# ControllerBoard.net
KiCad netlist of a schematic drawn in EAGLE
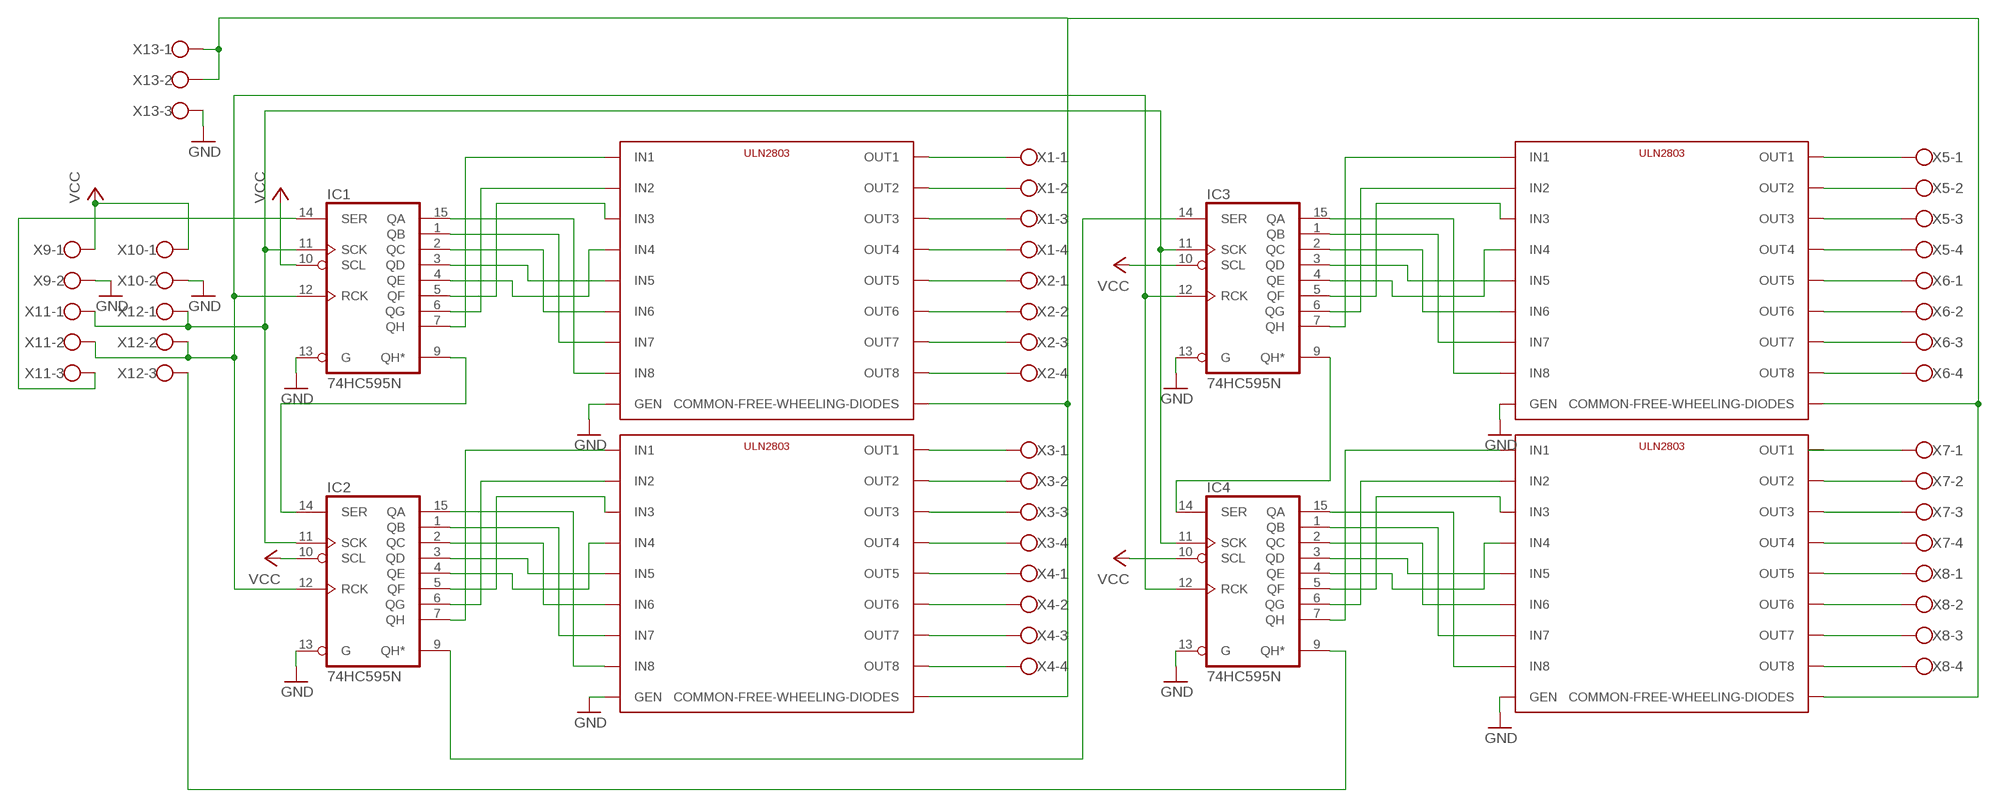
[diagram p0: schematic, sheet 1]

(export (version "E")
  (design (tool "Eeschema 10.0.6"))
  (components
    (comp (ref "IC1")
      (value "74HC595N")
      (footprint "eagle-import:DIL16")
      (libsource (lib "eagle-import") (part "74595NHC"))
    )
    (comp (ref "IC2")
      (value "74HC595N")
      (footprint "eagle-import:DIL16")
      (libsource (lib "eagle-import") (part "74595NHC"))
    )
    (comp (ref "IC3")
      (value "74HC595N")
      (footprint "eagle-import:DIL16")
      (libsource (lib "eagle-import") (part "74595NHC"))
    )
    (comp (ref "IC4")
      (value "74HC595N")
      (footprint "eagle-import:DIL16")
      (libsource (lib "eagle-import") (part "74595NHC"))
    )
    (comp (ref "U$1")
      (value "ULN2803")
      (footprint "eagle-import:P-DIP")
      (libsource (lib "eagle-import") (part "ULN2803"))
    )
    (comp (ref "U$2")
      (value "ULN2803")
      (footprint "eagle-import:P-DIP")
      (libsource (lib "eagle-import") (part "ULN2803"))
    )
    (comp (ref "U$3")
      (value "ULN2803")
      (footprint "eagle-import:P-DIP")
      (libsource (lib "eagle-import") (part "ULN2803"))
    )
    (comp (ref "U$4")
      (value "ULN2803")
      (footprint "eagle-import:P-DIP")
      (libsource (lib "eagle-import") (part "ULN2803"))
    )
    (comp (ref "X1")
      (value "W237-4")
      (footprint "eagle-import:W237-4")
      (libsource (lib "eagle-import") (part "W237-4"))
    )
    (comp (ref "X2")
      (value "W237-4")
      (footprint "eagle-import:W237-4")
      (libsource (lib "eagle-import") (part "W237-4"))
    )
    (comp (ref "X3")
      (value "W237-4")
      (footprint "eagle-import:W237-4")
      (libsource (lib "eagle-import") (part "W237-4"))
    )
    (comp (ref "X4")
      (value "W237-4")
      (footprint "eagle-import:W237-4")
      (libsource (lib "eagle-import") (part "W237-4"))
    )
    (comp (ref "X5")
      (value "W237-4")
      (footprint "eagle-import:W237-4")
      (libsource (lib "eagle-import") (part "W237-4"))
    )
    (comp (ref "X6")
      (value "W237-4")
      (footprint "eagle-import:W237-4")
      (libsource (lib "eagle-import") (part "W237-4"))
    )
    (comp (ref "X7")
      (value "W237-4")
      (footprint "eagle-import:W237-4")
      (libsource (lib "eagle-import") (part "W237-4"))
    )
    (comp (ref "X8")
      (value "W237-4")
      (footprint "eagle-import:W237-4")
      (libsource (lib "eagle-import") (part "W237-4"))
    )
    (comp (ref "X9")
      (value "W237-102")
      (footprint "eagle-import:W237-102")
      (fields (field (name "MPN") "237-102"))
      (libsource (lib "eagle-import") (part "W237-102"))
    )
    (comp (ref "X10")
      (value "W237-102")
      (footprint "eagle-import:W237-102")
      (fields (field (name "MPN") "237-102"))
      (libsource (lib "eagle-import") (part "W237-102"))
    )
    (comp (ref "X11")
      (value "W237-103")
      (footprint "eagle-import:W237-103")
      (fields (field (name "MPN") "237-103"))
      (libsource (lib "eagle-import") (part "W237-103"))
    )
    (comp (ref "X12")
      (value "W237-103")
      (footprint "eagle-import:W237-103")
      (fields (field (name "MPN") "237-103"))
      (libsource (lib "eagle-import") (part "W237-103"))
    )
    (comp (ref "X13")
      (value "W237-103")
      (footprint "eagle-import:W237-103")
      (fields (field (name "MPN") "237-103"))
      (libsource (lib "eagle-import") (part "W237-103"))
    )
  )
  (nets
    (net (code "1") (name "GND") (class "Default")
      (node (ref "IC1") (pin "13") (pinfunction "G_13") (pintype "input"))
      (node (ref "IC2") (pin "13") (pinfunction "G_13") (pintype "input"))
      (node (ref "IC3") (pin "13") (pinfunction "G_13") (pintype "input"))
      (node (ref "IC4") (pin "13") (pinfunction "G_13") (pintype "input"))
      (node (ref "U$1") (pin "GEN") (pinfunction "GEN_GEN") (pintype "power_in"))
      (node (ref "U$2") (pin "GEN") (pinfunction "GEN_GEN") (pintype "power_in"))
      (node (ref "U$3") (pin "GEN") (pinfunction "GEN_GEN") (pintype "power_in"))
      (node (ref "U$4") (pin "GEN") (pinfunction "GEN_GEN") (pintype "power_in"))
      (node (ref "X10") (pin "2") (pinfunction "KL_2") (pintype "passive"))
      (node (ref "X13") (pin "3") (pinfunction "KL_3") (pintype "passive"))
      (node (ref "X9") (pin "2") (pinfunction "KL_2") (pintype "passive"))
    )
    (net (code "2") (name "Net-(IC1A-QA)") (class "Default")
      (node (ref "IC1") (pin "15") (pinfunction "QA_15") (pintype "tri_state"))
      (node (ref "U$1") (pin "IN8") (pinfunction "IN8_IN8") (pintype "input"))
    )
    (net (code "3") (name "Net-(IC1A-QB)") (class "Default")
      (node (ref "IC1") (pin "1") (pinfunction "QB_1") (pintype "tri_state"))
      (node (ref "U$1") (pin "IN7") (pinfunction "IN7_IN7") (pintype "input"))
    )
    (net (code "4") (name "Net-(IC1A-QC)") (class "Default")
      (node (ref "IC1") (pin "2") (pinfunction "QC_2") (pintype "tri_state"))
      (node (ref "U$1") (pin "IN6") (pinfunction "IN6_IN6") (pintype "input"))
    )
    (net (code "5") (name "Net-(IC1A-QD)") (class "Default")
      (node (ref "IC1") (pin "3") (pinfunction "QD_3") (pintype "tri_state"))
      (node (ref "U$1") (pin "IN5") (pinfunction "IN5_IN5") (pintype "input"))
    )
    (net (code "6") (name "Net-(IC1A-QE)") (class "Default")
      (node (ref "IC1") (pin "4") (pinfunction "QE_4") (pintype "tri_state"))
      (node (ref "U$1") (pin "IN4") (pinfunction "IN4_IN4") (pintype "input"))
    )
    (net (code "7") (name "Net-(IC1A-QF)") (class "Default")
      (node (ref "IC1") (pin "5") (pinfunction "QF_5") (pintype "tri_state"))
      (node (ref "U$1") (pin "IN3") (pinfunction "IN3_IN3") (pintype "input"))
    )
    (net (code "8") (name "Net-(IC1A-QG)") (class "Default")
      (node (ref "IC1") (pin "6") (pinfunction "QG_6") (pintype "tri_state"))
      (node (ref "U$1") (pin "IN2") (pinfunction "IN2_IN2") (pintype "input"))
    )
    (net (code "9") (name "Net-(IC1A-QH)") (class "Default")
      (node (ref "IC1") (pin "7") (pinfunction "QH_7") (pintype "tri_state"))
      (node (ref "U$1") (pin "IN1") (pinfunction "IN1_IN1") (pintype "input"))
    )
    (net (code "10") (name "Net-(IC1A-QH*)") (class "Default")
      (node (ref "IC1") (pin "9") (pinfunction "QH*_9") (pintype "tri_state"))
      (node (ref "IC2") (pin "14") (pinfunction "SER_14") (pintype "input"))
    )
    (net (code "11") (name "Net-(IC1A-RCK)") (class "Default")
      (node (ref "IC1") (pin "12") (pinfunction "RCK_12") (pintype "input"))
      (node (ref "IC2") (pin "12") (pinfunction "RCK_12") (pintype "input"))
      (node (ref "IC3") (pin "12") (pinfunction "RCK_12") (pintype "input"))
      (node (ref "IC4") (pin "12") (pinfunction "RCK_12") (pintype "input"))
      (node (ref "X11") (pin "2") (pinfunction "KL_2") (pintype "passive"))
      (node (ref "X12") (pin "2") (pinfunction "KL_2") (pintype "passive"))
    )
    (net (code "12") (name "Net-(IC1A-SCK)") (class "Default")
      (node (ref "IC1") (pin "11") (pinfunction "SCK_11") (pintype "input"))
      (node (ref "IC2") (pin "11") (pinfunction "SCK_11") (pintype "input"))
      (node (ref "IC3") (pin "11") (pinfunction "SCK_11") (pintype "input"))
      (node (ref "IC4") (pin "11") (pinfunction "SCK_11") (pintype "input"))
      (node (ref "X11") (pin "1") (pinfunction "KL_1") (pintype "passive"))
      (node (ref "X12") (pin "1") (pinfunction "KL_1") (pintype "passive"))
    )
    (net (code "13") (name "Net-(IC1A-SER)") (class "Default")
      (node (ref "IC1") (pin "14") (pinfunction "SER_14") (pintype "input"))
      (node (ref "X11") (pin "3") (pinfunction "KL_3") (pintype "passive"))
    )
    (net (code "14") (name "Net-(IC2A-QA)") (class "Default")
      (node (ref "IC2") (pin "15") (pinfunction "QA_15") (pintype "tri_state"))
      (node (ref "U$3") (pin "IN8") (pinfunction "IN8_IN8") (pintype "input"))
    )
    (net (code "15") (name "Net-(IC2A-QB)") (class "Default")
      (node (ref "IC2") (pin "1") (pinfunction "QB_1") (pintype "tri_state"))
      (node (ref "U$3") (pin "IN7") (pinfunction "IN7_IN7") (pintype "input"))
    )
    (net (code "16") (name "Net-(IC2A-QC)") (class "Default")
      (node (ref "IC2") (pin "2") (pinfunction "QC_2") (pintype "tri_state"))
      (node (ref "U$3") (pin "IN6") (pinfunction "IN6_IN6") (pintype "input"))
    )
    (net (code "17") (name "Net-(IC2A-QD)") (class "Default")
      (node (ref "IC2") (pin "3") (pinfunction "QD_3") (pintype "tri_state"))
      (node (ref "U$3") (pin "IN5") (pinfunction "IN5_IN5") (pintype "input"))
    )
    (net (code "18") (name "Net-(IC2A-QE)") (class "Default")
      (node (ref "IC2") (pin "4") (pinfunction "QE_4") (pintype "tri_state"))
      (node (ref "U$3") (pin "IN4") (pinfunction "IN4_IN4") (pintype "input"))
    )
    (net (code "19") (name "Net-(IC2A-QF)") (class "Default")
      (node (ref "IC2") (pin "5") (pinfunction "QF_5") (pintype "tri_state"))
      (node (ref "U$3") (pin "IN3") (pinfunction "IN3_IN3") (pintype "input"))
    )
    (net (code "20") (name "Net-(IC2A-QG)") (class "Default")
      (node (ref "IC2") (pin "6") (pinfunction "QG_6") (pintype "tri_state"))
      (node (ref "U$3") (pin "IN2") (pinfunction "IN2_IN2") (pintype "input"))
    )
    (net (code "21") (name "Net-(IC2A-QH)") (class "Default")
      (node (ref "IC2") (pin "7") (pinfunction "QH_7") (pintype "tri_state"))
      (node (ref "U$3") (pin "IN1") (pinfunction "IN1_IN1") (pintype "input"))
    )
    (net (code "22") (name "Net-(IC2A-QH*)") (class "Default")
      (node (ref "IC2") (pin "9") (pinfunction "QH*_9") (pintype "tri_state"))
      (node (ref "IC3") (pin "14") (pinfunction "SER_14") (pintype "input"))
    )
    (net (code "23") (name "Net-(IC3A-QA)") (class "Default")
      (node (ref "IC3") (pin "15") (pinfunction "QA_15") (pintype "tri_state"))
      (node (ref "U$2") (pin "IN8") (pinfunction "IN8_IN8") (pintype "input"))
    )
    (net (code "24") (name "Net-(IC3A-QB)") (class "Default")
      (node (ref "IC3") (pin "1") (pinfunction "QB_1") (pintype "tri_state"))
      (node (ref "U$2") (pin "IN7") (pinfunction "IN7_IN7") (pintype "input"))
    )
    (net (code "25") (name "Net-(IC3A-QC)") (class "Default")
      (node (ref "IC3") (pin "2") (pinfunction "QC_2") (pintype "tri_state"))
      (node (ref "U$2") (pin "IN6") (pinfunction "IN6_IN6") (pintype "input"))
    )
    (net (code "26") (name "Net-(IC3A-QD)") (class "Default")
      (node (ref "IC3") (pin "3") (pinfunction "QD_3") (pintype "tri_state"))
      (node (ref "U$2") (pin "IN5") (pinfunction "IN5_IN5") (pintype "input"))
    )
    (net (code "27") (name "Net-(IC3A-QE)") (class "Default")
      (node (ref "IC3") (pin "4") (pinfunction "QE_4") (pintype "tri_state"))
      (node (ref "U$2") (pin "IN4") (pinfunction "IN4_IN4") (pintype "input"))
    )
    (net (code "28") (name "Net-(IC3A-QF)") (class "Default")
      (node (ref "IC3") (pin "5") (pinfunction "QF_5") (pintype "tri_state"))
      (node (ref "U$2") (pin "IN3") (pinfunction "IN3_IN3") (pintype "input"))
    )
    (net (code "29") (name "Net-(IC3A-QG)") (class "Default")
      (node (ref "IC3") (pin "6") (pinfunction "QG_6") (pintype "tri_state"))
      (node (ref "U$2") (pin "IN2") (pinfunction "IN2_IN2") (pintype "input"))
    )
    (net (code "30") (name "Net-(IC3A-QH)") (class "Default")
      (node (ref "IC3") (pin "7") (pinfunction "QH_7") (pintype "tri_state"))
      (node (ref "U$2") (pin "IN1") (pinfunction "IN1_IN1") (pintype "input"))
    )
    (net (code "31") (name "Net-(IC3A-QH*)") (class "Default")
      (node (ref "IC3") (pin "9") (pinfunction "QH*_9") (pintype "tri_state"))
      (node (ref "IC4") (pin "14") (pinfunction "SER_14") (pintype "input"))
    )
    (net (code "32") (name "Net-(IC4A-QA)") (class "Default")
      (node (ref "IC4") (pin "15") (pinfunction "QA_15") (pintype "tri_state"))
      (node (ref "U$4") (pin "IN8") (pinfunction "IN8_IN8") (pintype "input"))
    )
    (net (code "33") (name "Net-(IC4A-QB)") (class "Default")
      (node (ref "IC4") (pin "1") (pinfunction "QB_1") (pintype "tri_state"))
      (node (ref "U$4") (pin "IN7") (pinfunction "IN7_IN7") (pintype "input"))
    )
    (net (code "34") (name "Net-(IC4A-QC)") (class "Default")
      (node (ref "IC4") (pin "2") (pinfunction "QC_2") (pintype "tri_state"))
      (node (ref "U$4") (pin "IN6") (pinfunction "IN6_IN6") (pintype "input"))
    )
    (net (code "35") (name "Net-(IC4A-QD)") (class "Default")
      (node (ref "IC4") (pin "3") (pinfunction "QD_3") (pintype "tri_state"))
      (node (ref "U$4") (pin "IN5") (pinfunction "IN5_IN5") (pintype "input"))
    )
    (net (code "36") (name "Net-(IC4A-QE)") (class "Default")
      (node (ref "IC4") (pin "4") (pinfunction "QE_4") (pintype "tri_state"))
      (node (ref "U$4") (pin "IN4") (pinfunction "IN4_IN4") (pintype "input"))
    )
    (net (code "37") (name "Net-(IC4A-QF)") (class "Default")
      (node (ref "IC4") (pin "5") (pinfunction "QF_5") (pintype "tri_state"))
      (node (ref "U$4") (pin "IN3") (pinfunction "IN3_IN3") (pintype "input"))
    )
    (net (code "38") (name "Net-(IC4A-QG)") (class "Default")
      (node (ref "IC4") (pin "6") (pinfunction "QG_6") (pintype "tri_state"))
      (node (ref "U$4") (pin "IN2") (pinfunction "IN2_IN2") (pintype "input"))
    )
    (net (code "39") (name "Net-(IC4A-QH)") (class "Default")
      (node (ref "IC4") (pin "7") (pinfunction "QH_7") (pintype "tri_state"))
      (node (ref "U$4") (pin "IN1") (pinfunction "IN1_IN1") (pintype "input"))
    )
    (net (code "40") (name "Net-(IC4A-QH*)") (class "Default")
      (node (ref "IC4") (pin "9") (pinfunction "QH*_9") (pintype "tri_state"))
      (node (ref "X12") (pin "3") (pinfunction "KL_3") (pintype "passive"))
    )
    (net (code "41") (name "Net-(X1A-KL)") (class "Default")
      (node (ref "U$1") (pin "OUT1") (pinfunction "OUT1_OUT1") (pintype "output"))
      (node (ref "X1") (pin "1") (pinfunction "KL_1") (pintype "passive"))
    )
    (net (code "42") (name "Net-(X1B-KL)") (class "Default")
      (node (ref "U$1") (pin "OUT2") (pinfunction "OUT2_OUT2") (pintype "output"))
      (node (ref "X1") (pin "2") (pinfunction "KL_2") (pintype "passive"))
    )
    (net (code "43") (name "Net-(X1C-KL)") (class "Default")
      (node (ref "U$1") (pin "OUT3") (pinfunction "OUT3_OUT3") (pintype "output"))
      (node (ref "X1") (pin "3") (pinfunction "KL_3") (pintype "passive"))
    )
    (net (code "44") (name "Net-(X1D-KL)") (class "Default")
      (node (ref "U$1") (pin "OUT4") (pinfunction "OUT4_OUT4") (pintype "output"))
      (node (ref "X1") (pin "4") (pinfunction "KL_4") (pintype "passive"))
    )
    (net (code "45") (name "Net-(X2A-KL)") (class "Default")
      (node (ref "U$1") (pin "OUT5") (pinfunction "OUT5_OUT5") (pintype "output"))
      (node (ref "X2") (pin "1") (pinfunction "KL_1") (pintype "passive"))
    )
    (net (code "46") (name "Net-(X2B-KL)") (class "Default")
      (node (ref "U$1") (pin "OUT6") (pinfunction "OUT6_OUT6") (pintype "output"))
      (node (ref "X2") (pin "2") (pinfunction "KL_2") (pintype "passive"))
    )
    (net (code "47") (name "Net-(X2C-KL)") (class "Default")
      (node (ref "U$1") (pin "OUT7") (pinfunction "OUT7_OUT7") (pintype "output"))
      (node (ref "X2") (pin "3") (pinfunction "KL_3") (pintype "passive"))
    )
    (net (code "48") (name "Net-(X2D-KL)") (class "Default")
      (node (ref "U$1") (pin "OUT8") (pinfunction "OUT8_OUT8") (pintype "output"))
      (node (ref "X2") (pin "4") (pinfunction "KL_4") (pintype "passive"))
    )
    (net (code "49") (name "Net-(X3A-KL)") (class "Default")
      (node (ref "U$3") (pin "OUT1") (pinfunction "OUT1_OUT1") (pintype "output"))
      (node (ref "X3") (pin "1") (pinfunction "KL_1") (pintype "passive"))
    )
    (net (code "50") (name "Net-(X3B-KL)") (class "Default")
      (node (ref "U$3") (pin "OUT2") (pinfunction "OUT2_OUT2") (pintype "output"))
      (node (ref "X3") (pin "2") (pinfunction "KL_2") (pintype "passive"))
    )
    (net (code "51") (name "Net-(X3C-KL)") (class "Default")
      (node (ref "U$3") (pin "OUT3") (pinfunction "OUT3_OUT3") (pintype "output"))
      (node (ref "X3") (pin "3") (pinfunction "KL_3") (pintype "passive"))
    )
    (net (code "52") (name "Net-(X3D-KL)") (class "Default")
      (node (ref "U$3") (pin "OUT4") (pinfunction "OUT4_OUT4") (pintype "output"))
      (node (ref "X3") (pin "4") (pinfunction "KL_4") (pintype "passive"))
    )
    (net (code "53") (name "Net-(X4A-KL)") (class "Default")
      (node (ref "U$3") (pin "OUT5") (pinfunction "OUT5_OUT5") (pintype "output"))
      (node (ref "X4") (pin "1") (pinfunction "KL_1") (pintype "passive"))
    )
    (net (code "54") (name "Net-(X4B-KL)") (class "Default")
      (node (ref "U$3") (pin "OUT6") (pinfunction "OUT6_OUT6") (pintype "output"))
      (node (ref "X4") (pin "2") (pinfunction "KL_2") (pintype "passive"))
    )
    (net (code "55") (name "Net-(X4C-KL)") (class "Default")
      (node (ref "U$3") (pin "OUT7") (pinfunction "OUT7_OUT7") (pintype "output"))
      (node (ref "X4") (pin "3") (pinfunction "KL_3") (pintype "passive"))
    )
    (net (code "56") (name "Net-(X4D-KL)") (class "Default")
      (node (ref "U$3") (pin "OUT8") (pinfunction "OUT8_OUT8") (pintype "output"))
      (node (ref "X4") (pin "4") (pinfunction "KL_4") (pintype "passive"))
    )
    (net (code "57") (name "Net-(X5A-KL)") (class "Default")
      (node (ref "U$2") (pin "OUT1") (pinfunction "OUT1_OUT1") (pintype "output"))
      (node (ref "X5") (pin "1") (pinfunction "KL_1") (pintype "passive"))
    )
    (net (code "58") (name "Net-(X5B-KL)") (class "Default")
      (node (ref "U$2") (pin "OUT2") (pinfunction "OUT2_OUT2") (pintype "output"))
      (node (ref "X5") (pin "2") (pinfunction "KL_2") (pintype "passive"))
    )
    (net (code "59") (name "Net-(X5C-KL)") (class "Default")
      (node (ref "U$2") (pin "OUT3") (pinfunction "OUT3_OUT3") (pintype "output"))
      (node (ref "X5") (pin "3") (pinfunction "KL_3") (pintype "passive"))
    )
    (net (code "60") (name "Net-(X5D-KL)") (class "Default")
      (node (ref "U$2") (pin "OUT4") (pinfunction "OUT4_OUT4") (pintype "output"))
      (node (ref "X5") (pin "4") (pinfunction "KL_4") (pintype "passive"))
    )
    (net (code "61") (name "Net-(X6A-KL)") (class "Default")
      (node (ref "U$2") (pin "OUT5") (pinfunction "OUT5_OUT5") (pintype "output"))
      (node (ref "X6") (pin "1") (pinfunction "KL_1") (pintype "passive"))
    )
    (net (code "62") (name "Net-(X6B-KL)") (class "Default")
      (node (ref "U$2") (pin "OUT6") (pinfunction "OUT6_OUT6") (pintype "output"))
      (node (ref "X6") (pin "2") (pinfunction "KL_2") (pintype "passive"))
    )
    (net (code "63") (name "Net-(X6C-KL)") (class "Default")
      (node (ref "U$2") (pin "OUT7") (pinfunction "OUT7_OUT7") (pintype "output"))
      (node (ref "X6") (pin "3") (pinfunction "KL_3") (pintype "passive"))
    )
    (net (code "64") (name "Net-(X6D-KL)") (class "Default")
      (node (ref "U$2") (pin "OUT8") (pinfunction "OUT8_OUT8") (pintype "output"))
      (node (ref "X6") (pin "4") (pinfunction "KL_4") (pintype "passive"))
    )
    (net (code "65") (name "Net-(X7A-KL)") (class "Default")
      (node (ref "U$4") (pin "OUT1") (pinfunction "OUT1_OUT1") (pintype "output"))
      (node (ref "X7") (pin "1") (pinfunction "KL_1") (pintype "passive"))
    )
    (net (code "66") (name "Net-(X7B-KL)") (class "Default")
      (node (ref "U$4") (pin "OUT2") (pinfunction "OUT2_OUT2") (pintype "output"))
      (node (ref "X7") (pin "2") (pinfunction "KL_2") (pintype "passive"))
    )
    (net (code "67") (name "Net-(X7C-KL)") (class "Default")
      (node (ref "U$4") (pin "OUT3") (pinfunction "OUT3_OUT3") (pintype "output"))
      (node (ref "X7") (pin "3") (pinfunction "KL_3") (pintype "passive"))
    )
    (net (code "68") (name "Net-(X7D-KL)") (class "Default")
      (node (ref "U$4") (pin "OUT4") (pinfunction "OUT4_OUT4") (pintype "output"))
      (node (ref "X7") (pin "4") (pinfunction "KL_4") (pintype "passive"))
    )
    (net (code "69") (name "Net-(X8A-KL)") (class "Default")
      (node (ref "U$4") (pin "OUT5") (pinfunction "OUT5_OUT5") (pintype "output"))
      (node (ref "X8") (pin "1") (pinfunction "KL_1") (pintype "passive"))
    )
    (net (code "70") (name "Net-(X8B-KL)") (class "Default")
      (node (ref "U$4") (pin "OUT6") (pinfunction "OUT6_OUT6") (pintype "output"))
      (node (ref "X8") (pin "2") (pinfunction "KL_2") (pintype "passive"))
    )
    (net (code "71") (name "Net-(X8C-KL)") (class "Default")
      (node (ref "U$4") (pin "OUT7") (pinfunction "OUT7_OUT7") (pintype "output"))
      (node (ref "X8") (pin "3") (pinfunction "KL_3") (pintype "passive"))
    )
    (net (code "72") (name "Net-(X8D-KL)") (class "Default")
      (node (ref "U$4") (pin "OUT8") (pinfunction "OUT8_OUT8") (pintype "output"))
      (node (ref "X8") (pin "4") (pinfunction "KL_4") (pintype "passive"))
    )
    (net (code "73") (name "Net-(X13A-KL)") (class "Default")
      (node (ref "U$1") (pin "COMMON-FREE-WHEELING-DIODES") (pinfunction "COMMON-FREE-WHEELING-DIODES_COMMON-FREE-WHEELING-DIODES") (pintype "output"))
      (node (ref "U$2") (pin "COMMON-FREE-WHEELING-DIODES") (pinfunction "COMMON-FREE-WHEELING-DIODES_COMMON-FREE-WHEELING-DIODES") (pintype "output"))
      (node (ref "U$3") (pin "COMMON-FREE-WHEELING-DIODES") (pinfunction "COMMON-FREE-WHEELING-DIODES_COMMON-FREE-WHEELING-DIODES") (pintype "output"))
      (node (ref "U$4") (pin "COMMON-FREE-WHEELING-DIODES") (pinfunction "COMMON-FREE-WHEELING-DIODES_COMMON-FREE-WHEELING-DIODES") (pintype "output"))
      (node (ref "X13") (pin "1") (pinfunction "KL_1") (pintype "passive"))
      (node (ref "X13") (pin "2") (pinfunction "KL_2") (pintype "passive"))
    )
    (net (code "74") (name "VCC") (class "Default")
      (node (ref "IC1") (pin "10") (pinfunction "SCL_10") (pintype "input"))
      (node (ref "IC2") (pin "10") (pinfunction "SCL_10") (pintype "input"))
      (node (ref "IC3") (pin "10") (pinfunction "SCL_10") (pintype "input"))
      (node (ref "IC4") (pin "10") (pinfunction "SCL_10") (pintype "input"))
      (node (ref "X10") (pin "1") (pinfunction "KL_1") (pintype "passive"))
      (node (ref "X9") (pin "1") (pinfunction "KL_1") (pintype "passive"))
    )
  )
)
